# Sce_ES2_1.net
KiCad netlist of a schematic drawn in Altium Designer
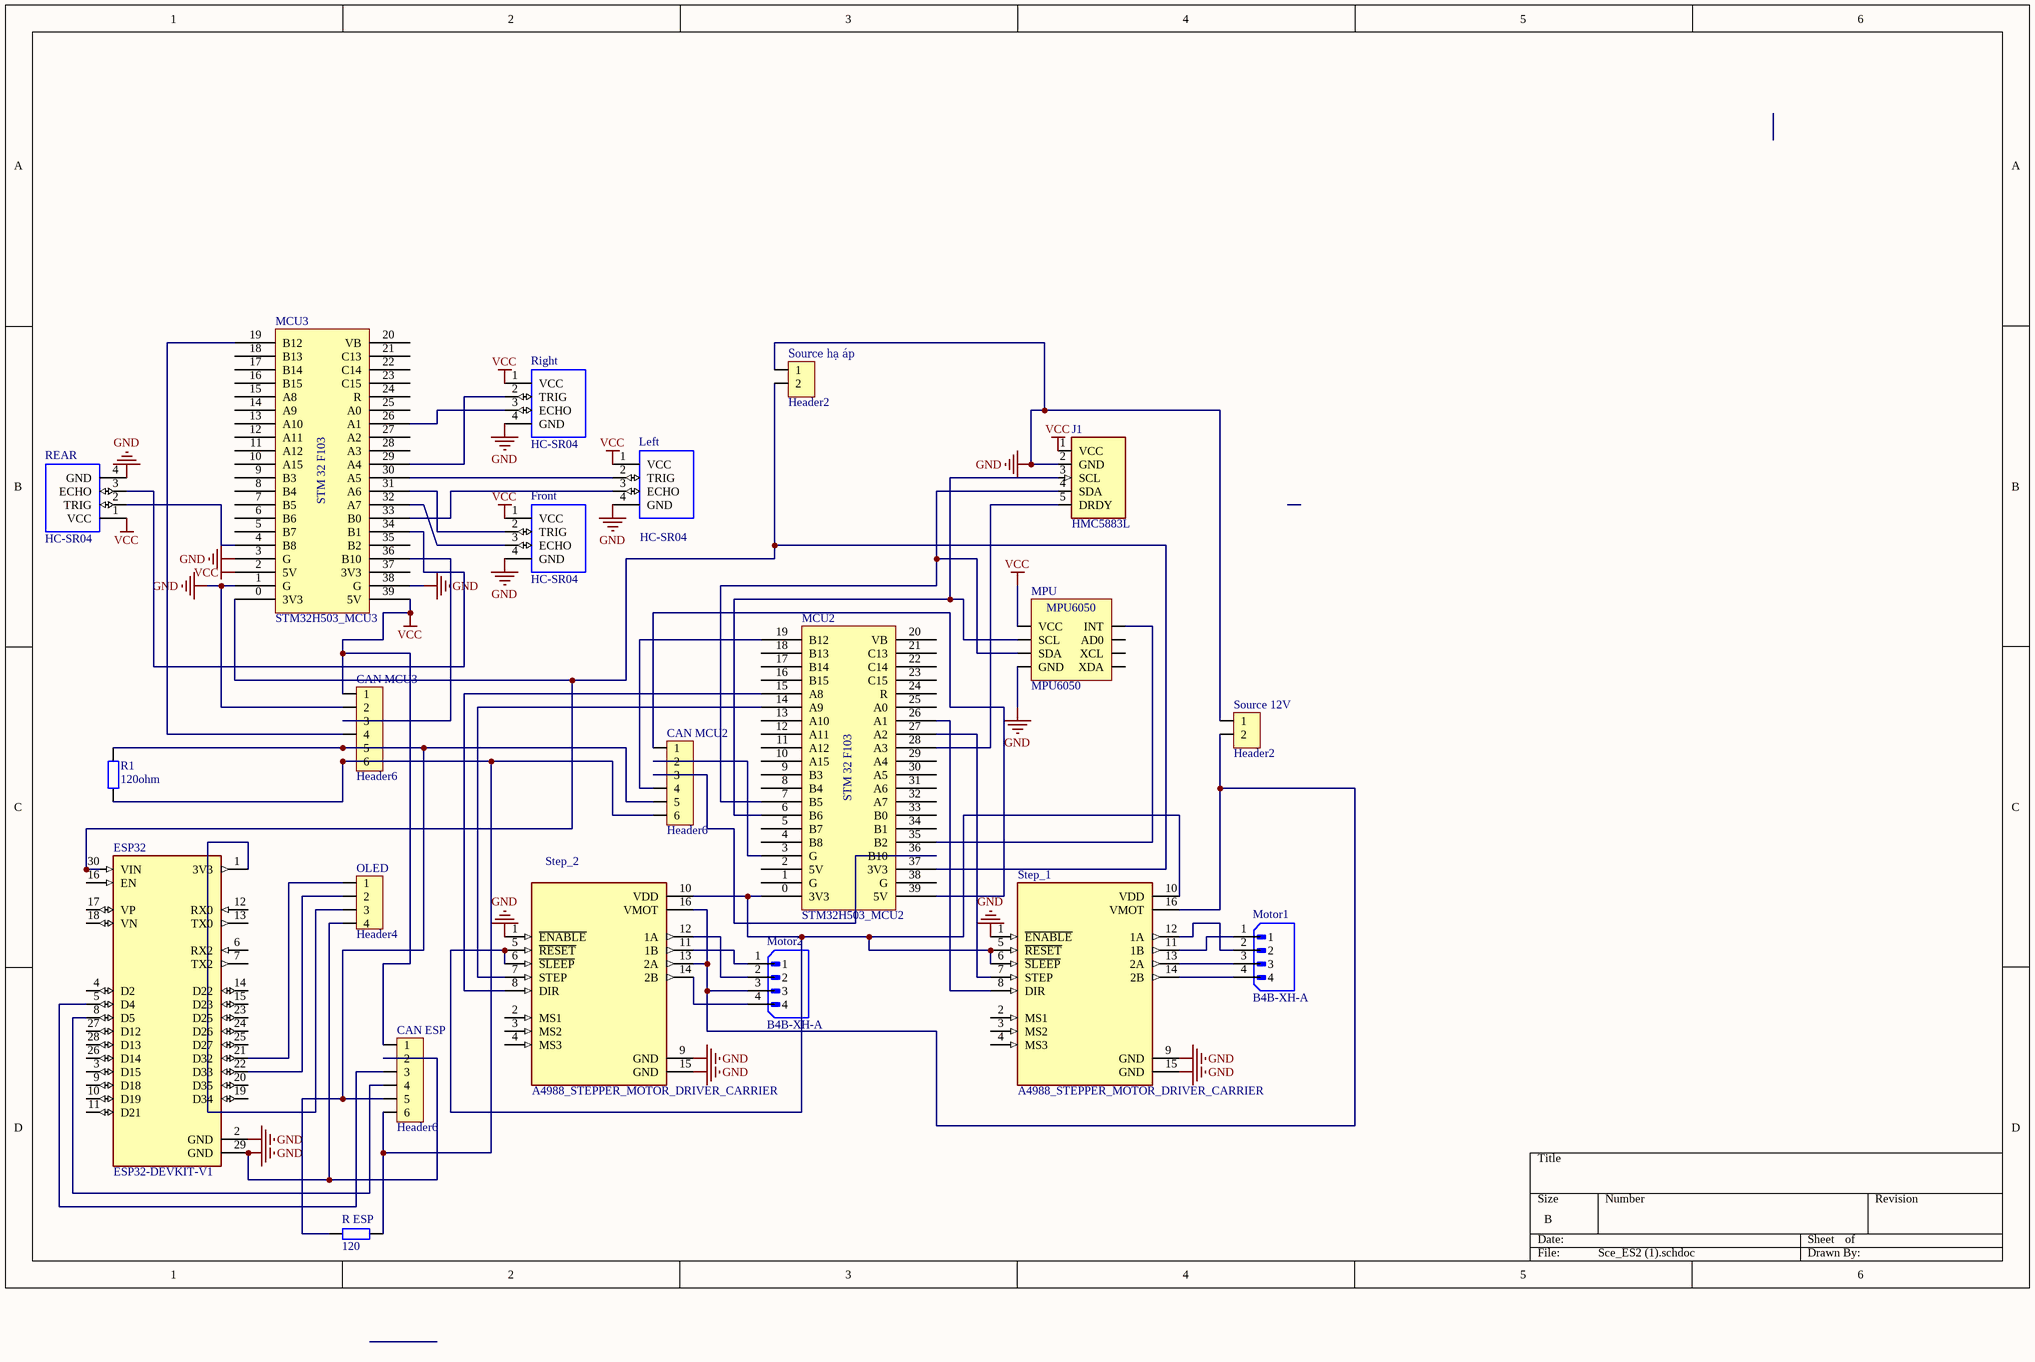
[diagram p0: Sce_ES2 (1).schdoc]

(export (version "E")
  (design (tool "Eeschema 10.0.6"))
  (components
    (comp (ref "CAN ESP")
      (value "Header6")
      (footprint "HDR6")
      (description "Header IDC, 6 x 1 Pin Vertical 2.54mm Pitch (Non-Boxed, Male)")
      (fields
        (field (name "MANUFACTURER") "Würth Elektronik eiSos GmbH")
        (field (name "PARTNO") "613002143121")
        (field (name "CREATED BY") "Karrer Zheng")
      )
      (libsource (lib "Library1") (part "Header6"))
    )
    (comp (ref "CAN MCU2")
      (value "Header6")
      (footprint "HDR6")
      (description "Header IDC, 6 x 1 Pin Vertical 2.54mm Pitch (Non-Boxed, Male)")
      (fields
        (field (name "MANUFACTURER") "Würth Elektronik eiSos GmbH")
        (field (name "PARTNO") "613002143121")
        (field (name "CREATED BY") "Karrer Zheng")
      )
      (libsource (lib "Library1") (part "Header6"))
    )
    (comp (ref "CAN MCU3")
      (value "Header6")
      (footprint "HDR6")
      (description "Header IDC, 6 x 1 Pin Vertical 2.54mm Pitch (Non-Boxed, Male)")
      (fields
        (field (name "MANUFACTURER") "Würth Elektronik eiSos GmbH")
        (field (name "PARTNO") "613002143121")
        (field (name "CREATED BY") "Karrer Zheng")
      )
      (libsource (lib "Library1") (part "Header6"))
    )
    (comp (ref "ESP32")
      (value "ESP32-DEVKIT-V1")
      (footprint "MODULE_ESP32_DEVKIT_V1")
      (fields (field (name "MF") "Do it"))
      (libsource (lib "ESP32-DEVKIT-V1") (part "ESP32-DEVKIT-V1"))
    )
    (comp (ref "Front")
      (value "HC-SR04")
      (footprint "XCVR_HC-SR04")
      (description "Ultrasonic Sensor Module")
      (libsource (lib "HC-SR04") (part "HC-SR04"))
    )
    (comp (ref "J1")
      (value "HMC5883L")
      (footprint "HMC5883L")
      (description "Magnetic Sensor Development Tools 3-Axis Digital Compass w 12-Bit ADC")
      (fields (field (name "MF") "STMicroelectronics"))
      (libsource (lib "HMC5883L") (part "HMC5883L"))
    )
    (comp (ref "Left")
      (value "HC-SR04")
      (footprint "XCVR_HC-SR04")
      (description "Ultrasonic Sensor Module")
      (libsource (lib "HC-SR04") (part "HC-SR04"))
    )
    (comp (ref "MCU2")
      (value "STM32H503_MCU2")
      (footprint "STM32F103")
      (libsource (lib "Library1") (part "STM32F103"))
    )
    (comp (ref "MCU3")
      (value "STM32H503_MCU3")
      (footprint "STM32F103")
      (libsource (lib "Library1") (part "STM32F103"))
    )
    (comp (ref "Motor1")
      (value "B4B-XH-A")
      (footprint "JST_B4B-XH-A")
      (description "Connector Header Through Hole 4 position 0.098 (2.50mm)")
      (fields (field (name "MF") "JST Sales"))
      (libsource (lib "B4B-XH-A") (part "B4B-XH-A"))
    )
    (comp (ref "Motor2")
      (value "B4B-XH-A")
      (footprint "JST_B4B-XH-A")
      (description "Connector Header Through Hole 4 position 0.098 (2.50mm)")
      (fields (field (name "MF") "JST Sales"))
      (libsource (lib "B4B-XH-A") (part "B4B-XH-A"))
    )
    (comp (ref "MPU")
      (value "MPU6050")
      (footprint "MPU6050")
      (fields
        (field (name "MANUFACTURER") "Würth Elektronik eiSos GmbH")
        (field (name "PARTNO") "613004143121")
        (field (name "CREATED BY") "Karrer Zheng")
      )
      (libsource (lib "Library1") (part "MPU6050"))
    )
    (comp (ref "OLED")
      (value "Header4")
      (footprint "HDR4")
      (description "Header IDC, 4 x 1 Pin Vertical 2.54mm Pitch (Non-Boxed, Male)")
      (fields
        (field (name "MANUFACTURER") "Würth Elektronik eiSos GmbH")
        (field (name "PARTNO") "613002143121")
        (field (name "CREATED BY") "Karrer Zheng")
      )
      (libsource (lib "Library1") (part "Header4"))
    )
    (comp (ref "R ESP")
      (value "120")
      (footprint "R1/2W")
      (description "Resistor 1/4W")
      (libsource (lib "syhaunguyen__1") (part "R1/4W"))
    )
    (comp (ref "R1")
      (value "120ohm")
      (footprint "R1/2W")
      (description "Resistor 1/4W")
      (libsource (lib "syhaunguyen__1") (part "R1/4W"))
    )
    (comp (ref "REAR")
      (value "HC-SR04")
      (footprint "XCVR_HC-SR04")
      (description "Ultrasonic Sensor Module")
      (libsource (lib "HC-SR04") (part "HC-SR04"))
    )
    (comp (ref "Right")
      (value "HC-SR04")
      (footprint "XCVR_HC-SR04")
      (description "Ultrasonic Sensor Module")
      (libsource (lib "HC-SR04") (part "HC-SR04"))
    )
    (comp (ref "Source 12V")
      (value "Header2")
      (footprint "HDR2")
      (description "Header IDC, 2 x 1 Pin Vertical 2.54mm Pitch (Non-Boxed, Male)")
      (fields
        (field (name "MANUFACTURER") "Würth Elektronik eiSos GmbH")
        (field (name "PARTNO") "613002143121")
        (field (name "CREATED BY") "Karrer Zheng")
      )
      (libsource (lib "Library1") (part "Header2"))
    )
    (comp (ref "Source hạ áp")
      (value "Header2")
      (footprint "HDR2")
      (description "Header IDC, 2 x 1 Pin Vertical 2.54mm Pitch (Non-Boxed, Male)")
      (fields
        (field (name "MANUFACTURER") "Würth Elektronik eiSos GmbH")
        (field (name "PARTNO") "613002143121")
        (field (name "CREATED BY") "Karrer Zheng")
      )
      (libsource (lib "Library1") (part "Header2"))
    )
    (comp (ref "Step_1")
      (value "A4988_STEPPER_MOTOR_DRIVER_CARRIER")
      (footprint "MODULE_A4988_STEPPER_MOTOR_DRIVER_CARRIER")
      (description "Stepper motor controler; IC: A4988; 1A; Uin mot: 8Ã·35V")
      (libsource (lib "A4988_STEPPER_MOTOR_DRIVER_CARRIER") (part "A4988_STEPPER_MOTOR_DRIVER_CARRIER"))
    )
    (comp (ref "Step_2")
      (value "A4988_STEPPER_MOTOR_DRIVER_CARRIER")
      (footprint "MODULE_A4988_STEPPER_MOTOR_DRIVER_CARRIER")
      (description "Stepper motor controler; IC: A4988; 1A; Uin mot: 8Ã·35V")
      (libsource (lib "A4988_STEPPER_MOTOR_DRIVER_CARRIER") (part "A4988_STEPPER_MOTOR_DRIVER_CARRIER"))
    )
  )
  (nets
    (net (code "1") (name "GND") (class "Default")
      (node (ref "CAN ESP") (pin "2") (pinfunction "2_2") (pintype "passive"))
      (node (ref "CAN MCU3") (pin "2") (pinfunction "2_2") (pintype "passive"))
      (node (ref "ESP32") (pin "2") (pinfunction "GND_2") (pintype "power_in"))
      (node (ref "ESP32") (pin "29") (pinfunction "GND_29") (pintype "power_in"))
      (node (ref "Front") (pin "4") (pinfunction "GND_4") (pintype "power_in"))
      (node (ref "J1") (pin "2") (pinfunction "GND_2") (pintype "power_in"))
      (node (ref "Left") (pin "4") (pinfunction "GND_4") (pintype "power_in"))
      (node (ref "MCU3") (pin "1") (pinfunction "G_1") (pintype "passive"))
      (node (ref "MCU3") (pin "3") (pinfunction "G_3") (pintype "passive"))
      (node (ref "MCU3") (pin "38") (pinfunction "G_38") (pintype "passive"))
      (node (ref "MPU") (pin "2") (pinfunction "GND_2") (pintype "passive"))
      (node (ref "OLED") (pin "4") (pinfunction "4_4") (pintype "passive"))
      (node (ref "REAR") (pin "4") (pinfunction "GND_4") (pintype "power_in"))
      (node (ref "Right") (pin "4") (pinfunction "GND_4") (pintype "power_in"))
      (node (ref "Source 12V") (pin "1") (pinfunction "1_1") (pintype "passive"))
      (node (ref "Source hạ áp") (pin "1") (pinfunction "1_1") (pintype "passive"))
      (node (ref "Step_1") (pin "1") (pinfunction "~{ENABLE}_1") (pintype "input"))
      (node (ref "Step_1") (pin "15") (pinfunction "GND_15") (pintype "power_in"))
      (node (ref "Step_1") (pin "9") (pinfunction "GND_9") (pintype "power_in"))
      (node (ref "Step_2") (pin "1") (pinfunction "~{ENABLE}_1") (pintype "input"))
      (node (ref "Step_2") (pin "15") (pinfunction "GND_15") (pintype "power_in"))
      (node (ref "Step_2") (pin "9") (pinfunction "GND_9") (pintype "power_in"))
    )
    (net (code "2") (name "Net-(CAN ESP-Pad5)") (class "Default")
      (node (ref "CAN ESP") (pin "5") (pinfunction "5_5") (pintype "passive"))
      (node (ref "CAN MCU2") (pin "5") (pinfunction "5_5") (pintype "passive"))
      (node (ref "CAN MCU3") (pin "5") (pinfunction "5_5") (pintype "passive"))
      (node (ref "R ESP") (pin "1") (pinfunction "1_1") (pintype "passive"))
      (node (ref "R1") (pin "2") (pinfunction "2_2") (pintype "passive"))
    )
    (net (code "3") (name "Net-(CAN ESP-Pad6)") (class "Default")
      (node (ref "CAN ESP") (pin "6") (pinfunction "6_6") (pintype "passive"))
      (node (ref "CAN MCU2") (pin "6") (pinfunction "6_6") (pintype "passive"))
      (node (ref "CAN MCU3") (pin "6") (pinfunction "6_6") (pintype "passive"))
      (node (ref "R ESP") (pin "2") (pinfunction "2_2") (pintype "passive"))
      (node (ref "R1") (pin "1") (pinfunction "1_1") (pintype "passive"))
    )
    (net (code "4") (name "Net-(CAN MCU2-Pad1)") (class "Default")
      (node (ref "CAN MCU2") (pin "1") (pinfunction "1_1") (pintype "passive"))
      (node (ref "MCU2") (pin "39") (pinfunction "5V_39") (pintype "passive"))
    )
    (net (code "5") (name "Net-(CAN MCU2-Pad2)") (class "Default")
      (node (ref "CAN MCU2") (pin "2") (pinfunction "2_2") (pintype "passive"))
      (node (ref "MCU2") (pin "3") (pinfunction "G_3") (pintype "passive"))
    )
    (net (code "6") (name "Net-(ESP32-3V3)") (class "Default")
      (node (ref "ESP32") (pin "1") (pinfunction "3V3_1") (pintype "output"))
      (node (ref "OLED") (pin "3") (pinfunction "3_3") (pintype "passive"))
    )
    (net (code "7") (name "Net-(ESP32-D4)") (class "Default")
      (node (ref "CAN ESP") (pin "3") (pinfunction "3_3") (pintype "passive"))
      (node (ref "ESP32") (pin "5") (pinfunction "D4_5") (pintype "bidirectional"))
    )
    (net (code "8") (name "Net-(ESP32-D5)") (class "Default")
      (node (ref "CAN ESP") (pin "4") (pinfunction "4_4") (pintype "passive"))
      (node (ref "ESP32") (pin "8") (pinfunction "D5_8") (pintype "bidirectional"))
    )
    (net (code "9") (name "Net-(ESP32-D32)") (class "Default")
      (node (ref "ESP32") (pin "21") (pinfunction "D32_21") (pintype "bidirectional"))
      (node (ref "OLED") (pin "1") (pinfunction "1_1") (pintype "passive"))
    )
    (net (code "10") (name "Net-(ESP32-D33)") (class "Default")
      (node (ref "ESP32") (pin "22") (pinfunction "D33_22") (pintype "bidirectional"))
      (node (ref "OLED") (pin "2") (pinfunction "2_2") (pintype "passive"))
    )
    (net (code "11") (name "Net-(ESP32-VIN)") (class "Default")
      (node (ref "ESP32") (pin "30") (pinfunction "VIN_30") (pintype "input"))
      (node (ref "MCU2") (pin "37") (pinfunction "3V3_37") (pintype "passive"))
      (node (ref "MCU3") (pin "0") (pinfunction "3V3_0") (pintype "passive"))
      (node (ref "Source hạ áp") (pin "2") (pinfunction "2_2") (pintype "passive"))
    )
    (net (code "12") (name "Net-(Front-ECHO)") (class "Default")
      (node (ref "Front") (pin "3") (pinfunction "ECHO_3") (pintype "bidirectional"))
      (node (ref "MCU3") (pin "32") (pinfunction "A7_32") (pintype "passive"))
    )
    (net (code "13") (name "Net-(Front-TRIG)") (class "Default")
      (node (ref "Front") (pin "2") (pinfunction "TRIG_2") (pintype "bidirectional"))
      (node (ref "MCU3") (pin "31") (pinfunction "A6_31") (pintype "passive"))
    )
    (net (code "14") (name "Net-(J1-DRDY)") (class "Default")
      (node (ref "J1") (pin "5") (pinfunction "DRDY_5") (pintype "bidirectional"))
      (node (ref "MCU2") (pin "28") (pinfunction "A3_28") (pintype "passive"))
    )
    (net (code "15") (name "Net-(J1-SCL)") (class "Default")
      (node (ref "J1") (pin "3") (pinfunction "SCL_3") (pintype "input"))
      (node (ref "MCU2") (pin "6") (pinfunction "B6_6") (pintype "passive"))
      (node (ref "MPU") (pin "3") (pinfunction "SCL_3") (pintype "passive"))
    )
    (net (code "16") (name "Net-(J1-SDA)") (class "Default")
      (node (ref "J1") (pin "4") (pinfunction "SDA_4") (pintype "bidirectional"))
      (node (ref "MCU2") (pin "7") (pinfunction "B5_7") (pintype "passive"))
      (node (ref "MPU") (pin "4") (pinfunction "SDA_4") (pintype "passive"))
    )
    (net (code "17") (name "Net-(Left-ECHO)") (class "Default")
      (node (ref "Left") (pin "3") (pinfunction "ECHO_3") (pintype "bidirectional"))
      (node (ref "MCU3") (pin "33") (pinfunction "B0_33") (pintype "passive"))
    )
    (net (code "18") (name "Net-(Left-TRIG)") (class "Default")
      (node (ref "Left") (pin "2") (pinfunction "TRIG_2") (pintype "bidirectional"))
      (node (ref "MCU3") (pin "30") (pinfunction "A5_30") (pintype "passive"))
    )
    (net (code "19") (name "Net-(MCU2-A1)") (class "Default")
      (node (ref "MCU2") (pin "26") (pinfunction "A1_26") (pintype "passive"))
      (node (ref "Step_1") (pin "8") (pinfunction "DIR_8") (pintype "input"))
    )
    (net (code "20") (name "Net-(MCU2-A2)") (class "Default")
      (node (ref "MCU2") (pin "27") (pinfunction "A2_27") (pintype "passive"))
      (node (ref "Step_1") (pin "7") (pinfunction "STEP_7") (pintype "input"))
    )
    (net (code "21") (name "Net-(MCU2-A8)") (class "Default")
      (node (ref "MCU2") (pin "15") (pinfunction "A8_15") (pintype "passive"))
      (node (ref "Step_2") (pin "8") (pinfunction "DIR_8") (pintype "input"))
    )
    (net (code "22") (name "Net-(MCU2-A9)") (class "Default")
      (node (ref "MCU2") (pin "14") (pinfunction "A9_14") (pintype "passive"))
      (node (ref "Step_2") (pin "7") (pinfunction "STEP_7") (pintype "input"))
    )
    (net (code "23") (name "Net-(MCU2-B2)") (class "Default")
      (node (ref "MCU2") (pin "35") (pinfunction "B2_35") (pintype "passive"))
      (node (ref "MPU") (pin "8") (pinfunction "INT_8") (pintype "passive"))
    )
    (net (code "24") (name "Net-(MCU2-B10)") (class "Default")
      (node (ref "CAN MCU2") (pin "3") (pinfunction "3_3") (pintype "passive"))
      (node (ref "MCU2") (pin "36") (pinfunction "B10_36") (pintype "passive"))
    )
    (net (code "25") (name "Net-(MCU2-B12)") (class "Default")
      (node (ref "CAN MCU2") (pin "4") (pinfunction "4_4") (pintype "passive"))
      (node (ref "MCU2") (pin "19") (pinfunction "B12_19") (pintype "passive"))
    )
    (net (code "26") (name "Net-(MCU3-A1)") (class "Default")
      (node (ref "MCU3") (pin "26") (pinfunction "A1_26") (pintype "passive"))
      (node (ref "Right") (pin "3") (pinfunction "ECHO_3") (pintype "bidirectional"))
    )
    (net (code "27") (name "Net-(MCU3-A4)") (class "Default")
      (node (ref "MCU3") (pin "29") (pinfunction "A4_29") (pintype "passive"))
      (node (ref "Right") (pin "2") (pinfunction "TRIG_2") (pintype "bidirectional"))
    )
    (net (code "28") (name "Net-(MCU3-B1)") (class "Default")
      (node (ref "MCU3") (pin "34") (pinfunction "B1_34") (pintype "passive"))
      (node (ref "REAR") (pin "3") (pinfunction "ECHO_3") (pintype "bidirectional"))
    )
    (net (code "29") (name "Net-(MCU3-B8)") (class "Default")
      (node (ref "MCU3") (pin "4") (pinfunction "B8_4") (pintype "passive"))
      (node (ref "REAR") (pin "2") (pinfunction "TRIG_2") (pintype "bidirectional"))
    )
    (net (code "30") (name "Net-(MCU3-B10)") (class "Default")
      (node (ref "CAN MCU3") (pin "3") (pinfunction "3_3") (pintype "passive"))
      (node (ref "MCU3") (pin "36") (pinfunction "B10_36") (pintype "passive"))
    )
    (net (code "31") (name "Net-(MCU3-B12)") (class "Default")
      (node (ref "CAN MCU3") (pin "4") (pinfunction "4_4") (pintype "passive"))
      (node (ref "MCU3") (pin "19") (pinfunction "B12_19") (pintype "passive"))
    )
    (net (code "32") (name "Net-(Step_1-1A)") (class "Default")
      (node (ref "Motor1") (pin "2") (pinfunction "2_2") (pintype "passive"))
      (node (ref "Step_1") (pin "12") (pinfunction "1A_12") (pintype "output"))
    )
    (net (code "33") (name "Net-(Step_1-1B)") (class "Default")
      (node (ref "Motor1") (pin "1") (pinfunction "1_1") (pintype "passive"))
      (node (ref "Step_1") (pin "11") (pinfunction "1B_11") (pintype "output"))
    )
    (net (code "34") (name "Net-(Step_1-2A)") (class "Default")
      (node (ref "Motor1") (pin "3") (pinfunction "3_3") (pintype "passive"))
      (node (ref "Step_1") (pin "13") (pinfunction "2A_13") (pintype "output"))
    )
    (net (code "35") (name "Net-(Step_1-2B)") (class "Default")
      (node (ref "Motor1") (pin "4") (pinfunction "4_4") (pintype "passive"))
      (node (ref "Step_1") (pin "14") (pinfunction "2B_14") (pintype "output"))
    )
    (net (code "36") (name "Net-(Step_1-VDD)") (class "Default")
      (node (ref "MCU2") (pin "0") (pinfunction "3V3_0") (pintype "passive"))
      (node (ref "Step_1") (pin "10") (pinfunction "VDD_10") (pintype "power_in"))
      (node (ref "Step_1") (pin "5") (pinfunction "~{RESET}_5") (pintype "input"))
      (node (ref "Step_1") (pin "6") (pinfunction "~{SLEEP}_6") (pintype "input"))
      (node (ref "Step_2") (pin "10") (pinfunction "VDD_10") (pintype "power_in"))
      (node (ref "Step_2") (pin "5") (pinfunction "~{RESET}_5") (pintype "input"))
      (node (ref "Step_2") (pin "6") (pinfunction "~{SLEEP}_6") (pintype "input"))
    )
    (net (code "37") (name "Net-(Step_1-VMOT)") (class "Default")
      (node (ref "Motor2") (pin "3") (pinfunction "3_3") (pintype "passive"))
      (node (ref "Source 12V") (pin "2") (pinfunction "2_2") (pintype "passive"))
      (node (ref "Step_1") (pin "16") (pinfunction "VMOT_16") (pintype "power_in"))
      (node (ref "Step_2") (pin "13") (pinfunction "2A_13") (pintype "output"))
      (node (ref "Step_2") (pin "16") (pinfunction "VMOT_16") (pintype "power_in"))
    )
    (net (code "38") (name "Net-(Step_2-1A)") (class "Default")
      (node (ref "Motor2") (pin "2") (pinfunction "2_2") (pintype "passive"))
      (node (ref "Step_2") (pin "12") (pinfunction "1A_12") (pintype "output"))
    )
    (net (code "39") (name "Net-(Step_2-1B)") (class "Default")
      (node (ref "Motor2") (pin "1") (pinfunction "1_1") (pintype "passive"))
      (node (ref "Step_2") (pin "11") (pinfunction "1B_11") (pintype "output"))
    )
    (net (code "40") (name "Net-(Step_2-2B)") (class "Default")
      (node (ref "Motor2") (pin "4") (pinfunction "4_4") (pintype "passive"))
      (node (ref "Step_2") (pin "14") (pinfunction "2B_14") (pintype "output"))
    )
    (net (code "41") (name "VCC") (class "Default")
      (node (ref "CAN ESP") (pin "1") (pinfunction "1_1") (pintype "passive"))
      (node (ref "CAN MCU3") (pin "1") (pinfunction "1_1") (pintype "passive"))
      (node (ref "Front") (pin "1") (pinfunction "VCC_1") (pintype "power_in"))
      (node (ref "J1") (pin "1") (pinfunction "VCC_1") (pintype "power_in"))
      (node (ref "Left") (pin "1") (pinfunction "VCC_1") (pintype "power_in"))
      (node (ref "MCU3") (pin "2") (pinfunction "5V_2") (pintype "passive"))
      (node (ref "MCU3") (pin "39") (pinfunction "5V_39") (pintype "passive"))
      (node (ref "MPU") (pin "1") (pinfunction "VCC_1") (pintype "passive"))
      (node (ref "REAR") (pin "1") (pinfunction "VCC_1") (pintype "power_in"))
      (node (ref "Right") (pin "1") (pinfunction "VCC_1") (pintype "power_in"))
    )
    (net (code "42") (name "unconnected-(ESP32-D2-Pad4)") (class "Default")
      (node (ref "ESP32") (pin "4") (pinfunction "D2_4") (pintype "bidirectional"))
    )
    (net (code "43") (name "unconnected-(ESP32-D12-Pad27)") (class "Default")
      (node (ref "ESP32") (pin "27") (pinfunction "D12_27") (pintype "bidirectional"))
    )
    (net (code "44") (name "unconnected-(ESP32-D13-Pad28)") (class "Default")
      (node (ref "ESP32") (pin "28") (pinfunction "D13_28") (pintype "bidirectional"))
    )
    (net (code "45") (name "unconnected-(ESP32-D14-Pad26)") (class "Default")
      (node (ref "ESP32") (pin "26") (pinfunction "D14_26") (pintype "bidirectional"))
    )
    (net (code "46") (name "unconnected-(ESP32-D15-Pad3)") (class "Default")
      (node (ref "ESP32") (pin "3") (pinfunction "D15_3") (pintype "bidirectional"))
    )
    (net (code "47") (name "unconnected-(ESP32-D18-Pad9)") (class "Default")
      (node (ref "ESP32") (pin "9") (pinfunction "D18_9") (pintype "bidirectional"))
    )
    (net (code "48") (name "unconnected-(ESP32-D19-Pad10)") (class "Default")
      (node (ref "ESP32") (pin "10") (pinfunction "D19_10") (pintype "bidirectional"))
    )
    (net (code "49") (name "unconnected-(ESP32-D21-Pad11)") (class "Default")
      (node (ref "ESP32") (pin "11") (pinfunction "D21_11") (pintype "bidirectional"))
    )
    (net (code "50") (name "unconnected-(ESP32-D22-Pad14)") (class "Default")
      (node (ref "ESP32") (pin "14") (pinfunction "D22_14") (pintype "bidirectional"))
    )
    (net (code "51") (name "unconnected-(ESP32-D23-Pad15)") (class "Default")
      (node (ref "ESP32") (pin "15") (pinfunction "D23_15") (pintype "bidirectional"))
    )
    (net (code "52") (name "unconnected-(ESP32-D25-Pad23)") (class "Default")
      (node (ref "ESP32") (pin "23") (pinfunction "D25_23") (pintype "bidirectional"))
    )
    (net (code "53") (name "unconnected-(ESP32-D26-Pad24)") (class "Default")
      (node (ref "ESP32") (pin "24") (pinfunction "D26_24") (pintype "bidirectional"))
    )
    (net (code "54") (name "unconnected-(ESP32-D27-Pad25)") (class "Default")
      (node (ref "ESP32") (pin "25") (pinfunction "D27_25") (pintype "bidirectional"))
    )
    (net (code "55") (name "unconnected-(ESP32-D34-Pad19)") (class "Default")
      (node (ref "ESP32") (pin "19") (pinfunction "D34_19") (pintype "bidirectional"))
    )
    (net (code "56") (name "unconnected-(ESP32-D35-Pad20)") (class "Default")
      (node (ref "ESP32") (pin "20") (pinfunction "D35_20") (pintype "bidirectional"))
    )
    (net (code "57") (name "unconnected-(ESP32-EN-Pad16)") (class "Default")
      (node (ref "ESP32") (pin "16") (pinfunction "EN_16") (pintype "input"))
    )
    (net (code "58") (name "unconnected-(ESP32-RX0-Pad12)") (class "Default")
      (node (ref "ESP32") (pin "12") (pinfunction "RX0_12") (pintype "input"))
    )
    (net (code "59") (name "unconnected-(ESP32-RX2-Pad6)") (class "Default")
      (node (ref "ESP32") (pin "6") (pinfunction "RX2_6") (pintype "input"))
    )
    (net (code "60") (name "unconnected-(ESP32-TX0-Pad13)") (class "Default")
      (node (ref "ESP32") (pin "13") (pinfunction "TX0_13") (pintype "output"))
    )
    (net (code "61") (name "unconnected-(ESP32-TX2-Pad7)") (class "Default")
      (node (ref "ESP32") (pin "7") (pinfunction "TX2_7") (pintype "output"))
    )
    (net (code "62") (name "unconnected-(ESP32-VN-Pad18)") (class "Default")
      (node (ref "ESP32") (pin "18") (pinfunction "VN_18") (pintype "bidirectional"))
    )
    (net (code "63") (name "unconnected-(ESP32-VP-Pad17)") (class "Default")
      (node (ref "ESP32") (pin "17") (pinfunction "VP_17") (pintype "bidirectional"))
    )
    (net (code "64") (name "unconnected-(MCU2-5V-Pad2)") (class "Default")
      (node (ref "MCU2") (pin "2") (pinfunction "5V_2") (pintype "passive"))
    )
    (net (code "65") (name "unconnected-(MCU2-A0-Pad25)") (class "Default")
      (node (ref "MCU2") (pin "25") (pinfunction "A0_25") (pintype "passive"))
    )
    (net (code "66") (name "unconnected-(MCU2-A4-Pad29)") (class "Default")
      (node (ref "MCU2") (pin "29") (pinfunction "A4_29") (pintype "passive"))
    )
    (net (code "67") (name "unconnected-(MCU2-A5-Pad30)") (class "Default")
      (node (ref "MCU2") (pin "30") (pinfunction "A5_30") (pintype "passive"))
    )
    (net (code "68") (name "unconnected-(MCU2-A6-Pad31)") (class "Default")
      (node (ref "MCU2") (pin "31") (pinfunction "A6_31") (pintype "passive"))
    )
    (net (code "69") (name "unconnected-(MCU2-A7-Pad32)") (class "Default")
      (node (ref "MCU2") (pin "32") (pinfunction "A7_32") (pintype "passive"))
    )
    (net (code "70") (name "unconnected-(MCU2-A10-Pad13)") (class "Default")
      (node (ref "MCU2") (pin "13") (pinfunction "A10_13") (pintype "passive"))
    )
    (net (code "71") (name "unconnected-(MCU2-A11-Pad12)") (class "Default")
      (node (ref "MCU2") (pin "12") (pinfunction "A11_12") (pintype "passive"))
    )
    (net (code "72") (name "unconnected-(MCU2-A12-Pad11)") (class "Default")
      (node (ref "MCU2") (pin "11") (pinfunction "A12_11") (pintype "passive"))
    )
    (net (code "73") (name "unconnected-(MCU2-A15-Pad10)") (class "Default")
      (node (ref "MCU2") (pin "10") (pinfunction "A15_10") (pintype "passive"))
    )
    (net (code "74") (name "unconnected-(MCU2-B0-Pad33)") (class "Default")
      (node (ref "MCU2") (pin "33") (pinfunction "B0_33") (pintype "passive"))
    )
    (net (code "75") (name "unconnected-(MCU2-B1-Pad34)") (class "Default")
      (node (ref "MCU2") (pin "34") (pinfunction "B1_34") (pintype "passive"))
    )
    (net (code "76") (name "unconnected-(MCU2-B3-Pad9)") (class "Default")
      (node (ref "MCU2") (pin "9") (pinfunction "B3_9") (pintype "passive"))
    )
    (net (code "77") (name "unconnected-(MCU2-B4-Pad8)") (class "Default")
      (node (ref "MCU2") (pin "8") (pinfunction "B4_8") (pintype "passive"))
    )
    (net (code "78") (name "unconnected-(MCU2-B7-Pad5)") (class "Default")
      (node (ref "MCU2") (pin "5") (pinfunction "B7_5") (pintype "passive"))
    )
    (net (code "79") (name "unconnected-(MCU2-B8-Pad4)") (class "Default")
      (node (ref "MCU2") (pin "4") (pinfunction "B8_4") (pintype "passive"))
    )
    (net (code "80") (name "unconnected-(MCU2-B13-Pad18)") (class "Default")
      (node (ref "MCU2") (pin "18") (pinfunction "B13_18") (pintype "passive"))
    )
    (net (code "81") (name "unconnected-(MCU2-B14-Pad17)") (class "Default")
      (node (ref "MCU2") (pin "17") (pinfunction "B14_17") (pintype "passive"))
    )
    (net (code "82") (name "unconnected-(MCU2-B15-Pad16)") (class "Default")
      (node (ref "MCU2") (pin "16") (pinfunction "B15_16") (pintype "passive"))
    )
    (net (code "83") (name "unconnected-(MCU2-C13-Pad21)") (class "Default")
      (node (ref "MCU2") (pin "21") (pinfunction "C13_21") (pintype "passive"))
    )
    (net (code "84") (name "unconnected-(MCU2-C14-Pad22)") (class "Default")
      (node (ref "MCU2") (pin "22") (pinfunction "C14_22") (pintype "passive"))
    )
    (net (code "85") (name "unconnected-(MCU2-C15-Pad23)") (class "Default")
      (node (ref "MCU2") (pin "23") (pinfunction "C15_23") (pintype "passive"))
    )
    (net (code "86") (name "unconnected-(MCU2-G-Pad1)") (class "Default")
      (node (ref "MCU2") (pin "1") (pinfunction "G_1") (pintype "passive"))
    )
    (net (code "87") (name "unconnected-(MCU2-G-Pad38)") (class "Default")
      (node (ref "MCU2") (pin "38") (pinfunction "G_38") (pintype "passive"))
    )
    (net (code "88") (name "unconnected-(MCU2-R-Pad24)") (class "Default")
      (node (ref "MCU2") (pin "24") (pinfunction "R_24") (pintype "passive"))
    )
    (net (code "89") (name "unconnected-(MCU2-VB-Pad20)") (class "Default")
      (node (ref "MCU2") (pin "20") (pinfunction "VB_20") (pintype "passive"))
    )
    (net (code "90") (name "unconnected-(MCU3-3V3-Pad37)") (class "Default")
      (node (ref "MCU3") (pin "37") (pinfunction "3V3_37") (pintype "passive"))
    )
    (net (code "91") (name "unconnected-(MCU3-A0-Pad25)") (class "Default")
      (node (ref "MCU3") (pin "25") (pinfunction "A0_25") (pintype "passive"))
    )
    (net (code "92") (name "unconnected-(MCU3-A2-Pad27)") (class "Default")
      (node (ref "MCU3") (pin "27") (pinfunction "A2_27") (pintype "passive"))
    )
    (net (code "93") (name "unconnected-(MCU3-A3-Pad28)") (class "Default")
      (node (ref "MCU3") (pin "28") (pinfunction "A3_28") (pintype "passive"))
    )
    (net (code "94") (name "unconnected-(MCU3-A8-Pad15)") (class "Default")
      (node (ref "MCU3") (pin "15") (pinfunction "A8_15") (pintype "passive"))
    )
    (net (code "95") (name "unconnected-(MCU3-A9-Pad14)") (class "Default")
      (node (ref "MCU3") (pin "14") (pinfunction "A9_14") (pintype "passive"))
    )
    (net (code "96") (name "unconnected-(MCU3-A10-Pad13)") (class "Default")
      (node (ref "MCU3") (pin "13") (pinfunction "A10_13") (pintype "passive"))
    )
    (net (code "97") (name "unconnected-(MCU3-A11-Pad12)") (class "Default")
      (node (ref "MCU3") (pin "12") (pinfunction "A11_12") (pintype "passive"))
    )
    (net (code "98") (name "unconnected-(MCU3-A12-Pad11)") (class "Default")
      (node (ref "MCU3") (pin "11") (pinfunction "A12_11") (pintype "passive"))
    )
    (net (code "99") (name "unconnected-(MCU3-A15-Pad10)") (class "Default")
      (node (ref "MCU3") (pin "10") (pinfunction "A15_10") (pintype "passive"))
    )
    (net (code "100") (name "unconnected-(MCU3-B2-Pad35)") (class "Default")
      (node (ref "MCU3") (pin "35") (pinfunction "B2_35") (pintype "passive"))
    )
    (net (code "101") (name "unconnected-(MCU3-B3-Pad9)") (class "Default")
      (node (ref "MCU3") (pin "9") (pinfunction "B3_9") (pintype "passive"))
    )
    (net (code "102") (name "unconnected-(MCU3-B4-Pad8)") (class "Default")
      (node (ref "MCU3") (pin "8") (pinfunction "B4_8") (pintype "passive"))
    )
    (net (code "103") (name "unconnected-(MCU3-B5-Pad7)") (class "Default")
      (node (ref "MCU3") (pin "7") (pinfunction "B5_7") (pintype "passive"))
    )
    (net (code "104") (name "unconnected-(MCU3-B6-Pad6)") (class "Default")
      (node (ref "MCU3") (pin "6") (pinfunction "B6_6") (pintype "passive"))
    )
    (net (code "105") (name "unconnected-(MCU3-B7-Pad5)") (class "Default")
      (node (ref "MCU3") (pin "5") (pinfunction "B7_5") (pintype "passive"))
    )
    (net (code "106") (name "unconnected-(MCU3-B13-Pad18)") (class "Default")
      (node (ref "MCU3") (pin "18") (pinfunction "B13_18") (pintype "passive"))
    )
    (net (code "107") (name "unconnected-(MCU3-B14-Pad17)") (class "Default")
      (node (ref "MCU3") (pin "17") (pinfunction "B14_17") (pintype "passive"))
    )
    (net (code "108") (name "unconnected-(MCU3-B15-Pad16)") (class "Default")
      (node (ref "MCU3") (pin "16") (pinfunction "B15_16") (pintype "passive"))
    )
    (net (code "109") (name "unconnected-(MCU3-C13-Pad21)") (class "Default")
      (node (ref "MCU3") (pin "21") (pinfunction "C13_21") (pintype "passive"))
    )
    (net (code "110") (name "unconnected-(MCU3-C14-Pad22)") (class "Default")
      (node (ref "MCU3") (pin "22") (pinfunction "C14_22") (pintype "passive"))
    )
    (net (code "111") (name "unconnected-(MCU3-C15-Pad23)") (class "Default")
      (node (ref "MCU3") (pin "23") (pinfunction "C15_23") (pintype "passive"))
    )
    (net (code "112") (name "unconnected-(MCU3-R-Pad24)") (class "Default")
      (node (ref "MCU3") (pin "24") (pinfunction "R_24") (pintype "passive"))
    )
    (net (code "113") (name "unconnected-(MCU3-VB-Pad20)") (class "Default")
      (node (ref "MCU3") (pin "20") (pinfunction "VB_20") (pintype "passive"))
    )
    (net (code "114") (name "unconnected-(MPU-AD0-Pad7)") (class "Default")
      (node (ref "MPU") (pin "7") (pinfunction "AD0_7") (pintype "passive"))
    )
    (net (code "115") (name "unconnected-(MPU-XCL-Pad6)") (class "Default")
      (node (ref "MPU") (pin "6") (pinfunction "XCL_6") (pintype "passive"))
    )
    (net (code "116") (name "unconnected-(MPU-XDA-Pad5)") (class "Default")
      (node (ref "MPU") (pin "5") (pinfunction "XDA_5") (pintype "passive"))
    )
    (net (code "117") (name "unconnected-(Step_1-MS1-Pad2)") (class "Default")
      (node (ref "Step_1") (pin "2") (pinfunction "MS1_2") (pintype "input"))
    )
    (net (code "118") (name "unconnected-(Step_1-MS2-Pad3)") (class "Default")
      (node (ref "Step_1") (pin "3") (pinfunction "MS2_3") (pintype "input"))
    )
    (net (code "119") (name "unconnected-(Step_1-MS3-Pad4)") (class "Default")
      (node (ref "Step_1") (pin "4") (pinfunction "MS3_4") (pintype "input"))
    )
    (net (code "120") (name "unconnected-(Step_2-MS1-Pad2)") (class "Default")
      (node (ref "Step_2") (pin "2") (pinfunction "MS1_2") (pintype "input"))
    )
    (net (code "121") (name "unconnected-(Step_2-MS2-Pad3)") (class "Default")
      (node (ref "Step_2") (pin "3") (pinfunction "MS2_3") (pintype "input"))
    )
    (net (code "122") (name "unconnected-(Step_2-MS3-Pad4)") (class "Default")
      (node (ref "Step_2") (pin "4") (pinfunction "MS3_4") (pintype "input"))
    )
  )
)
